# Scheme.net
KiCad netlist of a schematic drawn in Altium Designer
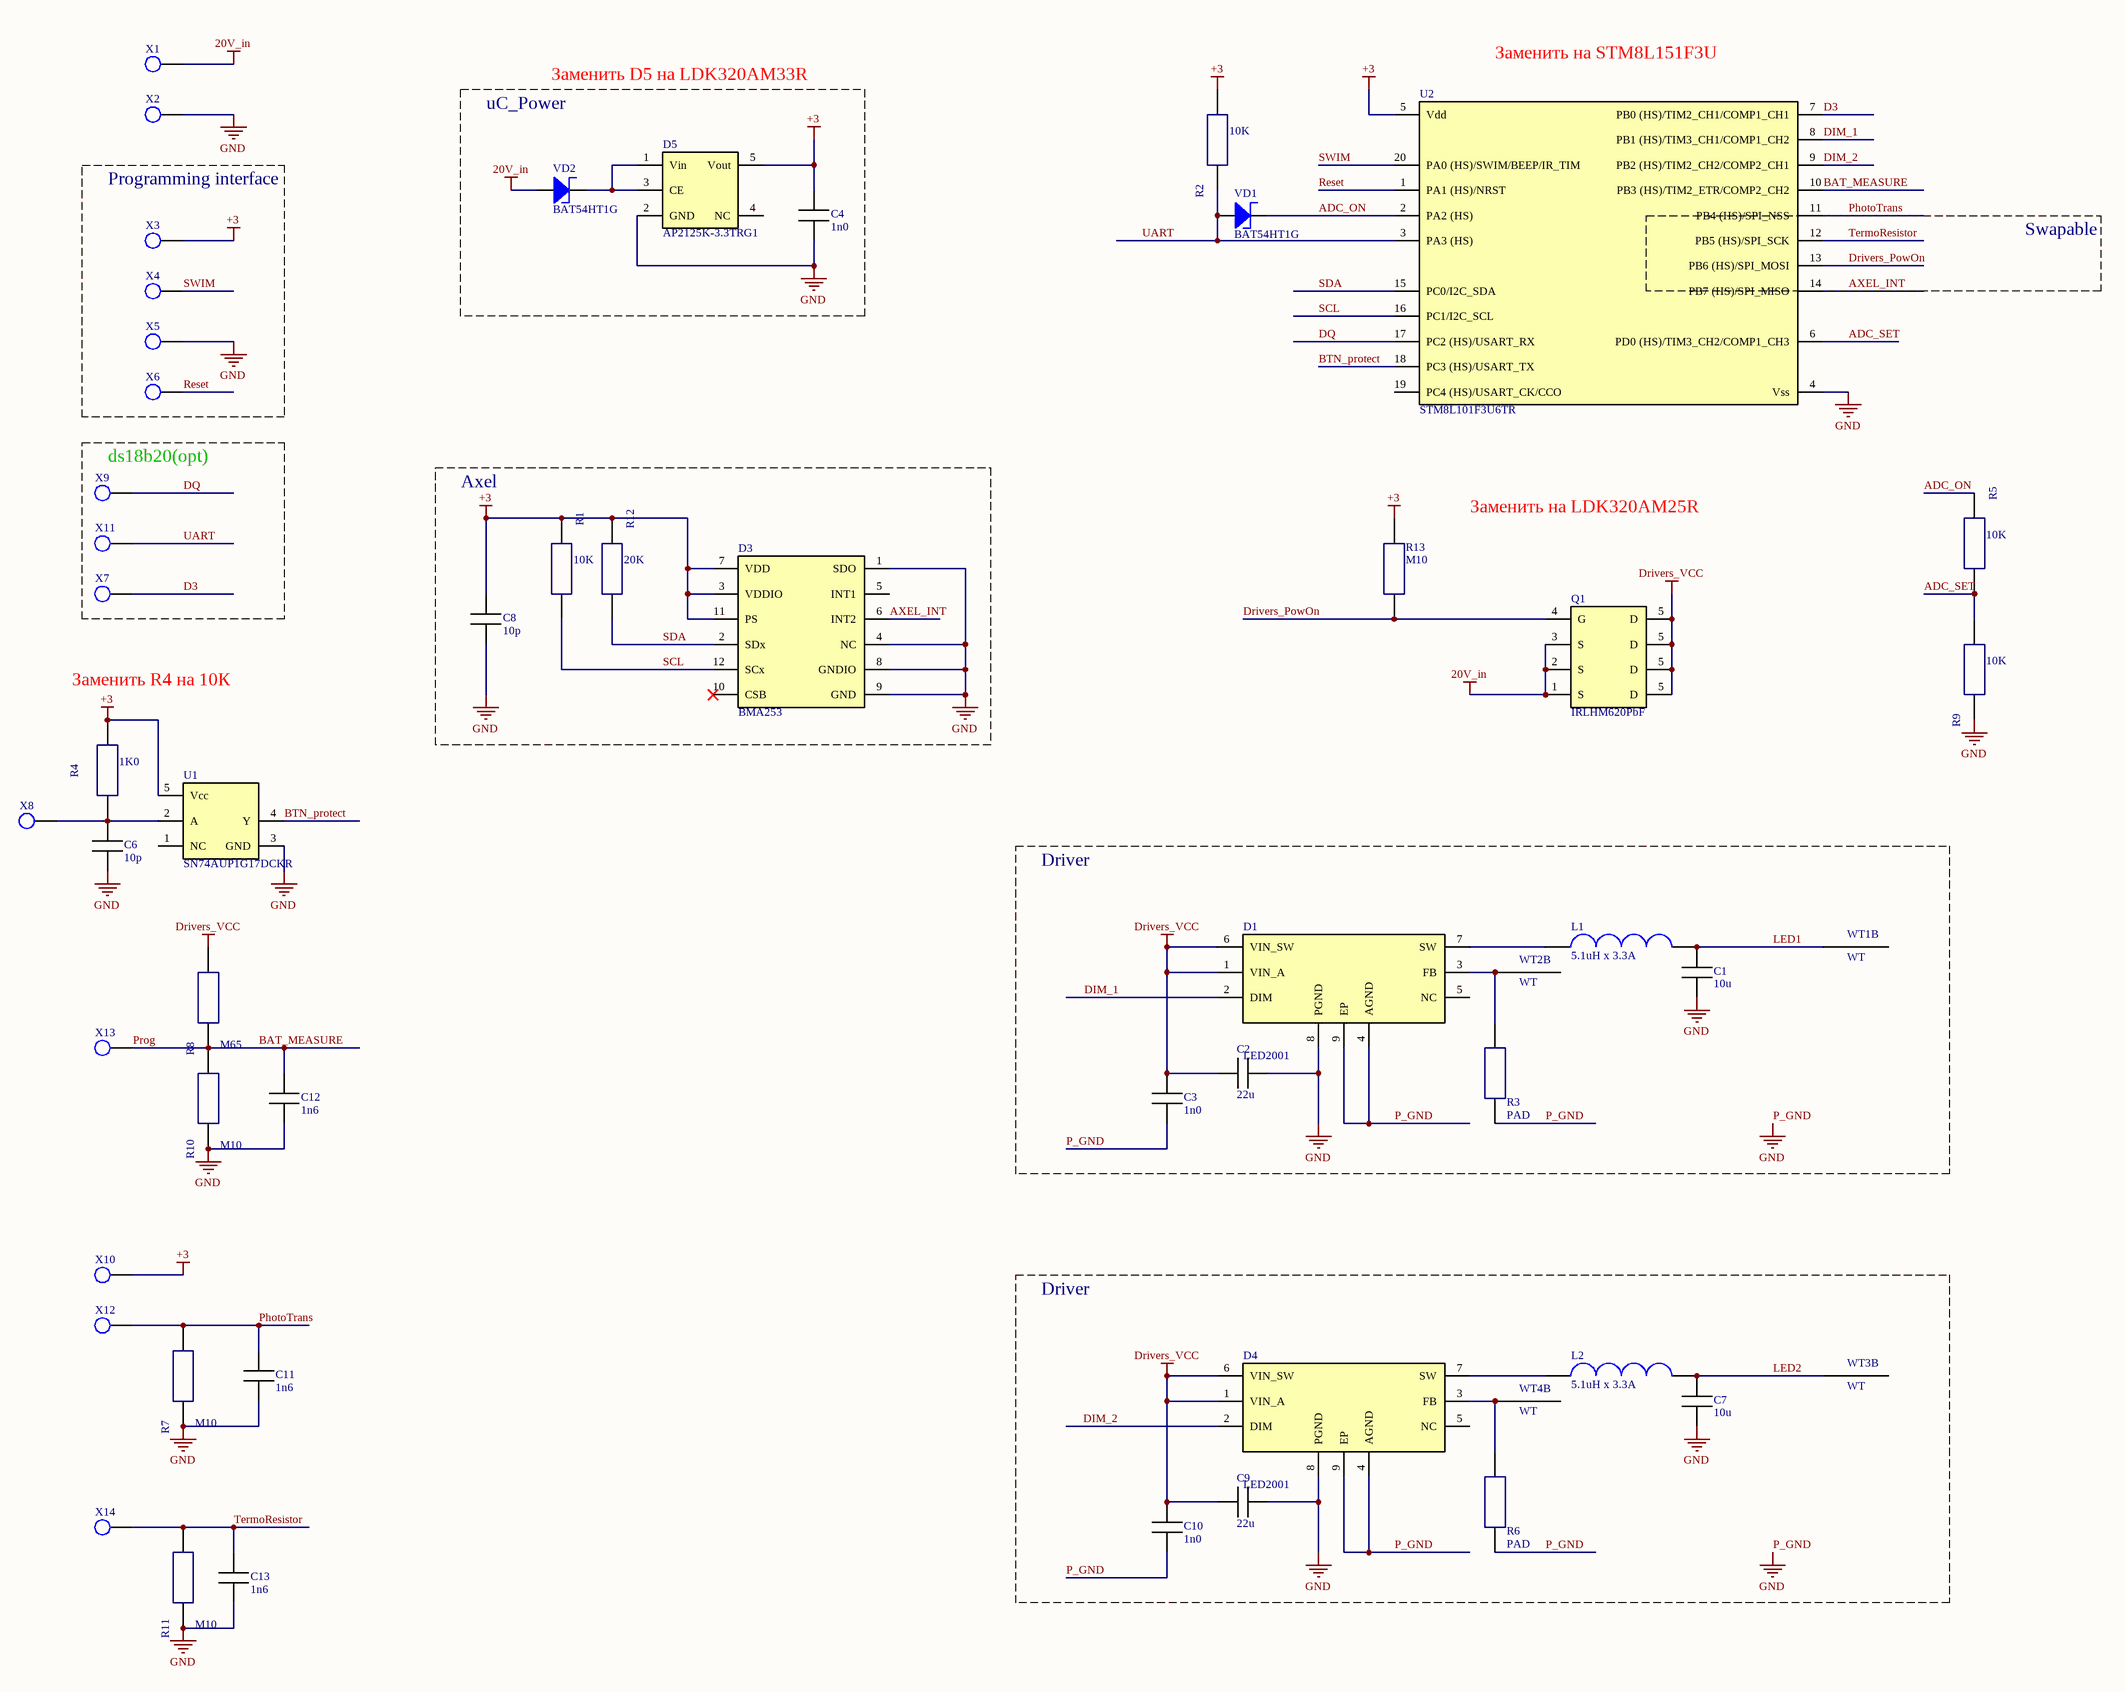
[diagram p0: Scheme.SchDoc]

(export (version "E")
  (design (tool "Eeschema 10.0.6"))
  (components
    (comp (ref "C1")
      (value "10u")
      (footprint "Cap 0603")
      (description "NO")
      (fields (field (name "VOLTAGE") "25V"))
      (libsource (lib "Altium Vault") (part "Capasitor Ceramic"))
    )
    (comp (ref "C2")
      (value "22u")
      (footprint "Cap 1206")
      (description "NO")
      (fields (field (name "VOLTAGE") "25V"))
      (libsource (lib "Altium Vault") (part "Capasitor Ceramic"))
    )
    (comp (ref "C3")
      (value "1n0")
      (footprint "Cap 0603")
      (description "1n x 50V")
      (fields (field (name "VOLTAGE") "50V"))
      (libsource (lib "Altium Vault") (part "Capasitor Ceramic"))
    )
    (comp (ref "C4")
      (value "1n0")
      (footprint "Cap 0603")
      (description "1n x 50V")
      (fields (field (name "VOLTAGE") "50V"))
      (libsource (lib "Altium Vault") (part "Capasitor Ceramic"))
    )
    (comp (ref "C6")
      (value "10p")
      (footprint "Cap 0603")
      (description "10p x 25V")
      (fields (field (name "VOLTAGE") "25V"))
      (libsource (lib "Altium Vault") (part "Capasitor Ceramic"))
    )
    (comp (ref "C7")
      (value "10u")
      (footprint "Cap 0603")
      (description "NO")
      (fields (field (name "VOLTAGE") "25V"))
      (libsource (lib "Altium Vault") (part "Capasitor Ceramic"))
    )
    (comp (ref "C8")
      (value "10p")
      (footprint "Cap 0603")
      (description "10p x 25V")
      (fields (field (name "VOLTAGE") "25V"))
      (libsource (lib "Altium Vault") (part "Capasitor Ceramic"))
    )
    (comp (ref "C9")
      (value "22u")
      (footprint "Cap 1206")
      (description "NO")
      (fields (field (name "VOLTAGE") "25V"))
      (libsource (lib "Altium Vault") (part "Capasitor Ceramic"))
    )
    (comp (ref "C10")
      (value "1n0")
      (footprint "Cap 0603")
      (description "1n x 50V")
      (fields (field (name "VOLTAGE") "50V"))
      (libsource (lib "Altium Vault") (part "Capasitor Ceramic"))
    )
    (comp (ref "C11")
      (value "1n6")
      (footprint "Cap 0603")
      (description "1n6 x 50V")
      (fields (field (name "VOLTAGE") "50V"))
      (libsource (lib "Altium Vault") (part "Capasitor Ceramic"))
    )
    (comp (ref "C12")
      (value "1n6")
      (footprint "Cap 0603")
      (description "1n6 x 50V")
      (fields (field (name "VOLTAGE") "50V"))
      (libsource (lib "Altium Vault") (part "Capasitor Ceramic"))
    )
    (comp (ref "C13")
      (value "1n6")
      (footprint "Cap 0603")
      (description "1n6 x 50V")
      (fields (field (name "VOLTAGE") "50V"))
      (libsource (lib "Altium Vault") (part "Capasitor Ceramic"))
    )
    (comp (ref "D1")
      (value "LED2001")
      (footprint "VQFPN-8 4x4")
      (libsource (lib "Altium Vault") (part "CMP-00546-6"))
    )
    (comp (ref "D3")
      (value "BMA253")
      (footprint "LGA-12 2x2x0.9")
      (libsource (lib "Altium Vault") (part "BMA250E"))
    )
    (comp (ref "D4")
      (value "LED2001")
      (footprint "VQFPN-8 4x4")
      (libsource (lib "Altium Vault") (part "CMP-00546-6"))
    )
    (comp (ref "D5")
      (value "AP2125K-3.3TRG1")
      (footprint "SOT23-5")
      (libsource (lib "Altium Vault") (part "AP2125K-2.8TRG1"))
    )
    (comp (ref "L1")
      (value "5.1uH x 3.3A")
      (footprint "ASPI-6045S-5R1N-T")
      (description "ASPI-6045S-5R1N-T, 5.1uH x 3.3A")
      (fields (field (name "Comment") "51"))
      (libsource (lib "Altium Vault") (part "Inductors"))
    )
    (comp (ref "L2")
      (value "5.1uH x 3.3A")
      (footprint "ASPI-6045S-5R1N-T")
      (description "ASPI-6045S-5R1N-T, 5.1uH x 3.3A")
      (fields (field (name "Comment") "51"))
      (libsource (lib "Altium Vault") (part "Inductors"))
    )
    (comp (ref "Q1")
      (value "IRLHM620PbF")
      (footprint "PQFN-8 3.3x3.3")
      (fields (field (name "Comment") "IRLHM620"))
      (libsource (lib "Altium Vault") (part "IRLHM620PbF"))
    )
    (comp (ref "R1")
      (value "10K")
      (footprint "R0603 5%")
      (description "R 10K")
      (fields (field (name "Comment") "103"))
      (libsource (lib "Altium Vault") (part "Resistors"))
    )
    (comp (ref "R2")
      (value "10K")
      (footprint "R0603 5%")
      (description "R 10K")
      (fields (field (name "Comment") "103"))
      (libsource (lib "Altium Vault") (part "Resistors"))
    )
    (comp (ref "R3")
      (value "PAD")
      (footprint "Resistor 1206")
      (libsource (lib "Altium Vault") (part "Resistors"))
    )
    (comp (ref "R4")
      (value "1K0")
      (footprint "R0603 5%")
      (description "R 1K0")
      (fields (field (name "Comment") "102"))
      (libsource (lib "Altium Vault") (part "Resistors"))
    )
    (comp (ref "R5")
      (value "10K")
      (footprint "R0603 5%")
      (description "R 10K")
      (fields (field (name "Comment") "103"))
      (libsource (lib "Altium Vault") (part "Resistors"))
    )
    (comp (ref "R6")
      (value "PAD")
      (footprint "Resistor 1206")
      (libsource (lib "Altium Vault") (part "Resistors"))
    )
    (comp (ref "R7")
      (value "M10")
      (footprint "R0603 5%")
      (description "R M10")
      (fields (field (name "Comment") "104"))
      (libsource (lib "Altium Vault") (part "Resistors"))
    )
    (comp (ref "R8")
      (value "M65")
      (footprint "R0603 5%")
      (description "R M65")
      (fields (field (name "Comment") "654"))
      (libsource (lib "Altium Vault") (part "Resistors"))
    )
    (comp (ref "R9")
      (value "10K")
      (footprint "R0603 5%")
      (description "R 10K")
      (fields (field (name "Comment") "103"))
      (libsource (lib "Altium Vault") (part "Resistors"))
    )
    (comp (ref "R10")
      (value "M10")
      (footprint "R0603 5%")
      (description "R M10")
      (fields (field (name "Comment") "104"))
      (libsource (lib "Altium Vault") (part "Resistors"))
    )
    (comp (ref "R11")
      (value "M10")
      (footprint "R0603 5%")
      (description "R M10")
      (fields (field (name "Comment") "104"))
      (libsource (lib "Altium Vault") (part "Resistors"))
    )
    (comp (ref "R12")
      (value "20K")
      (footprint "R0603 5%")
      (description "R 20K")
      (fields (field (name "Comment") "203"))
      (libsource (lib "Altium Vault") (part "Resistors"))
    )
    (comp (ref "R13")
      (value "M10")
      (footprint "R0603 5%")
      (description "R M10")
      (fields (field (name "Comment") "104"))
      (libsource (lib "Altium Vault") (part "Resistors"))
    )
    (comp (ref "U1")
      (value "SN74AUP1G17DCKR")
      (footprint "SC-70-5")
      (fields (field (name "Comment") "SN74AUP"))
      (libsource (lib "E-button") (part "SN74AUP1G17DCKR"))
    )
    (comp (ref "U2")
      (value "STM8L101F3U6TR")
      (footprint "UFQFPN20 3x3x0.5")
      (fields (field (name "Comment") "STM8L101"))
      (libsource (lib "Altium Vault") (part "STM8L101x1 UFQFPN-20"))
    )
    (comp (ref "VD1")
      (value "BAT54HT1G")
      (footprint "SOD323")
      (fields (field (name "Comment") "JV"))
      (libsource (lib "Altium Vault") (part "Schottky diode"))
    )
    (comp (ref "VD2")
      (value "BAT54HT1G")
      (footprint "SOD323")
      (fields (field (name "Comment") "JV"))
      (libsource (lib "Altium Vault") (part "Schottky diode"))
    )
    (comp (ref "WT1") (value "WT") (footprint "WT") (libsource (lib "Altium Vault") (part "WireTerminal")))
    (comp (ref "WT2") (value "WT") (footprint "WT") (libsource (lib "Altium Vault") (part "WireTerminal")))
    (comp (ref "WT3") (value "WT") (footprint "WT") (libsource (lib "Altium Vault") (part "WireTerminal")))
    (comp (ref "WT4") (value "WT") (footprint "WT") (libsource (lib "Altium Vault") (part "CMP-00159-3")))
    (comp (ref "X1")
      (value "*")
      (footprint "TP 0.8mm")
      (description "TP 0.8mm")
      (libsource (lib "Altium Vault") (part "Test point"))
    )
    (comp (ref "X2")
      (value "*")
      (footprint "TP 0.8mm")
      (description "TP 0.8mm")
      (libsource (lib "Altium Vault") (part "Test point"))
    )
    (comp (ref "X3")
      (value "*")
      (footprint "TP 0.8mm")
      (description "TP 0.8mm")
      (libsource (lib "Altium Vault") (part "Test point"))
    )
    (comp (ref "X4")
      (value "*")
      (footprint "TP 0.8mm")
      (description "TP 0.8mm")
      (libsource (lib "Altium Vault") (part "Test point"))
    )
    (comp (ref "X5")
      (value "*")
      (footprint "TP 0.8mm")
      (description "TP 0.8mm")
      (libsource (lib "Altium Vault") (part "Test point"))
    )
    (comp (ref "X6")
      (value "*")
      (footprint "TP 0.8mm")
      (description "TP 0.8mm")
      (libsource (lib "Altium Vault") (part "Test point"))
    )
    (comp (ref "X7")
      (value "*")
      (footprint "TP 0.8mm")
      (description "TP 0.8mm")
      (libsource (lib "Altium Vault") (part "Test point"))
    )
    (comp (ref "X8")
      (value "*")
      (footprint "TP 0.8mm")
      (description "TP 0.8mm")
      (libsource (lib "Altium Vault") (part "Test point"))
    )
    (comp (ref "X9")
      (value "*")
      (footprint "TP 0.8mm")
      (description "TP 0.8mm")
      (libsource (lib "Altium Vault") (part "Test point"))
    )
    (comp (ref "X10")
      (value "*")
      (footprint "TP 0.8mm")
      (description "TP 0.8mm")
      (libsource (lib "Altium Vault") (part "Test point"))
    )
    (comp (ref "X11")
      (value "*")
      (footprint "TP 0.8mm")
      (description "TP 0.8mm")
      (libsource (lib "Altium Vault") (part "Test point"))
    )
    (comp (ref "X12")
      (value "*")
      (footprint "TP 0.8mm")
      (description "TP 0.8mm")
      (libsource (lib "Altium Vault") (part "Test point"))
    )
    (comp (ref "X13")
      (value "*")
      (footprint "TP 0.8mm")
      (description "TP 0.8mm")
      (libsource (lib "Altium Vault") (part "Test point"))
    )
    (comp (ref "X14")
      (value "*")
      (footprint "TP 0.8mm")
      (description "TP 0.8mm")
      (libsource (lib "Altium Vault") (part "Test point"))
    )
  )
  (nets
    (net (code "1") (name "+3") (class "Default")
      (node (ref "C4") (pin "2") (pinfunction "2_2") (pintype "passive"))
      (node (ref "C8") (pin "2") (pinfunction "2_2") (pintype "passive"))
      (node (ref "D3") (pin "11") (pinfunction "PS_11") (pintype "passive"))
      (node (ref "D3") (pin "3") (pinfunction "VDDIO_3") (pintype "passive"))
      (node (ref "D3") (pin "7") (pinfunction "VDD_7") (pintype "passive"))
      (node (ref "D5") (pin "5") (pinfunction "Vout_5") (pintype "passive"))
      (node (ref "R1") (pin "1") (pinfunction "1_1") (pintype "passive"))
      (node (ref "R12") (pin "1") (pinfunction "1_1") (pintype "passive"))
      (node (ref "R13") (pin "2") (pinfunction "2_2") (pintype "passive"))
      (node (ref "R2") (pin "2") (pinfunction "2_2") (pintype "passive"))
      (node (ref "R4") (pin "2") (pinfunction "2_2") (pintype "passive"))
      (node (ref "U1") (pin "5") (pinfunction "Vcc_5") (pintype "passive"))
      (node (ref "U2") (pin "5") (pinfunction "Vdd_5") (pintype "passive"))
      (node (ref "X10") (pin "1") (pinfunction "1_1") (pintype "passive"))
      (node (ref "X3") (pin "1") (pinfunction "1_1") (pintype "passive"))
    )
    (net (code "2") (name "/ADC_ON") (class "Default")
      (node (ref "R5") (pin "1") (pinfunction "1_1") (pintype "passive"))
      (node (ref "U2") (pin "2") (pinfunction "PA2_(HS)_2") (pintype "passive"))
      (node (ref "VD1") (pin "1") (pinfunction "1_1") (pintype "passive"))
    )
    (net (code "3") (name "/ADC_SET") (class "Default")
      (node (ref "R5") (pin "2") (pinfunction "2_2") (pintype "passive"))
      (node (ref "R9") (pin "2") (pinfunction "2_2") (pintype "passive"))
      (node (ref "U2") (pin "6") (pinfunction "PD0_(HS)/TIM3_CH2/COMP1_CH3_6") (pintype "passive"))
    )
    (net (code "4") (name "/AXEL_INT") (class "Default")
      (node (ref "D3") (pin "6") (pinfunction "INT2_6") (pintype "passive"))
      (node (ref "U2") (pin "14") (pinfunction "PB7_(HS)/SPI_MISO_14") (pintype "passive"))
    )
    (net (code "5") (name "/BAT_MEASURE") (class "Default")
      (node (ref "C12") (pin "2") (pinfunction "2_2") (pintype "passive"))
      (node (ref "R10") (pin "2") (pinfunction "2_2") (pintype "passive"))
      (node (ref "R8") (pin "1") (pinfunction "1_1") (pintype "passive"))
      (node (ref "U2") (pin "10") (pinfunction "PB3_(HS)/TIM2_ETR/COMP2_CH2_10") (pintype "passive"))
      (node (ref "X13") (pin "1") (pinfunction "1_1") (pintype "passive"))
    )
    (net (code "6") (name "/BTN_protect") (class "Default")
      (node (ref "U1") (pin "4") (pinfunction "Y_4") (pintype "passive"))
      (node (ref "U2") (pin "18") (pinfunction "PC3_(HS)/USART_TX_18") (pintype "passive"))
    )
    (net (code "7") (name "/D3") (class "Default")
      (node (ref "U2") (pin "7") (pinfunction "PB0_(HS)/TIM2_CH1/COMP1_CH1_7") (pintype "passive"))
      (node (ref "X7") (pin "1") (pinfunction "1_1") (pintype "passive"))
    )
    (net (code "8") (name "/DIM_1") (class "Default")
      (node (ref "D1") (pin "2") (pinfunction "DIM_2") (pintype "passive"))
      (node (ref "U2") (pin "8") (pinfunction "PB1_(HS)/TIM3_CH1/COMP1_CH2_8") (pintype "passive"))
    )
    (net (code "9") (name "/DIM_2") (class "Default")
      (node (ref "D4") (pin "2") (pinfunction "DIM_2") (pintype "passive"))
      (node (ref "U2") (pin "9") (pinfunction "PB2_(HS)/TIM2_CH2/COMP2_CH1_9") (pintype "passive"))
    )
    (net (code "10") (name "/DQ") (class "Default")
      (node (ref "U2") (pin "17") (pinfunction "PC2_(HS)/USART_RX_17") (pintype "passive"))
      (node (ref "X9") (pin "1") (pinfunction "1_1") (pintype "passive"))
    )
    (net (code "11") (name "/Drivers_PowOn") (class "Default")
      (node (ref "Q1") (pin "4") (pinfunction "G_4") (pintype "passive"))
      (node (ref "R13") (pin "1") (pinfunction "1_1") (pintype "passive"))
      (node (ref "U2") (pin "13") (pinfunction "PB6_(HS)/SPI_MOSI_13") (pintype "passive"))
    )
    (net (code "12") (name "/LED1") (class "Default")
      (node (ref "C1") (pin "2") (pinfunction "2_2") (pintype "passive"))
      (node (ref "L1") (pin "2") (pinfunction "2_2") (pintype "passive"))
      (node (ref "WT1") (pin "1") (pinfunction "1_1") (pintype "passive"))
    )
    (net (code "13") (name "/LED2") (class "Default")
      (node (ref "C7") (pin "2") (pinfunction "2_2") (pintype "passive"))
      (node (ref "L2") (pin "2") (pinfunction "2_2") (pintype "passive"))
      (node (ref "WT3") (pin "1") (pinfunction "1_1") (pintype "passive"))
    )
    (net (code "14") (name "/PhotoTrans") (class "Default")
      (node (ref "C11") (pin "2") (pinfunction "2_2") (pintype "passive"))
      (node (ref "R7") (pin "2") (pinfunction "2_2") (pintype "passive"))
      (node (ref "U2") (pin "11") (pinfunction "PB4_(HS)/SPI_NSS_11") (pintype "passive"))
      (node (ref "X12") (pin "1") (pinfunction "1_1") (pintype "passive"))
    )
    (net (code "15") (name "/Reset") (class "Default")
      (node (ref "U2") (pin "1") (pinfunction "PA1_(HS)/NRST_1") (pintype "passive"))
      (node (ref "X6") (pin "1") (pinfunction "1_1") (pintype "passive"))
    )
    (net (code "16") (name "/SCL") (class "Default")
      (node (ref "D3") (pin "12") (pinfunction "SCx_12") (pintype "passive"))
      (node (ref "R1") (pin "2") (pinfunction "2_2") (pintype "passive"))
      (node (ref "U2") (pin "16") (pinfunction "PC1/I2C_SCL_16") (pintype "passive"))
    )
    (net (code "17") (name "/SDA") (class "Default")
      (node (ref "D3") (pin "2") (pinfunction "SDx_2") (pintype "passive"))
      (node (ref "R12") (pin "2") (pinfunction "2_2") (pintype "passive"))
      (node (ref "U2") (pin "15") (pinfunction "PC0/I2C_SDA_15") (pintype "passive"))
    )
    (net (code "18") (name "/SWIM") (class "Default")
      (node (ref "U2") (pin "20") (pinfunction "PA0_(HS)/SWIM/BEEP/IR_TIM_20") (pintype "passive"))
      (node (ref "X4") (pin "1") (pinfunction "1_1") (pintype "passive"))
    )
    (net (code "19") (name "/TermoResistor") (class "Default")
      (node (ref "C13") (pin "2") (pinfunction "2_2") (pintype "passive"))
      (node (ref "R11") (pin "2") (pinfunction "2_2") (pintype "passive"))
      (node (ref "U2") (pin "12") (pinfunction "PB5_(HS)/SPI_SCK_12") (pintype "passive"))
      (node (ref "X14") (pin "1") (pinfunction "1_1") (pintype "passive"))
    )
    (net (code "20") (name "/UART") (class "Default")
      (node (ref "R2") (pin "1") (pinfunction "1_1") (pintype "passive"))
      (node (ref "U2") (pin "3") (pinfunction "PA3_(HS)_3") (pintype "passive"))
      (node (ref "VD1") (pin "2") (pinfunction "2_2") (pintype "passive"))
      (node (ref "X11") (pin "1") (pinfunction "1_1") (pintype "passive"))
    )
    (net (code "21") (name "20V_in") (class "Default")
      (node (ref "Q1") (pin "1") (pinfunction "S_1") (pintype "passive"))
      (node (ref "Q1") (pin "2") (pinfunction "S_2") (pintype "passive"))
      (node (ref "Q1") (pin "3") (pinfunction "S_3") (pintype "passive"))
      (node (ref "VD2") (pin "2") (pinfunction "2_2") (pintype "passive"))
      (node (ref "X1") (pin "1") (pinfunction "1_1") (pintype "passive"))
    )
    (net (code "22") (name "Drivers_VCC") (class "Default")
      (node (ref "C10") (pin "2") (pinfunction "2_2") (pintype "passive"))
      (node (ref "C2") (pin "1") (pinfunction "1_1") (pintype "passive"))
      (node (ref "C3") (pin "2") (pinfunction "2_2") (pintype "passive"))
      (node (ref "C9") (pin "1") (pinfunction "1_1") (pintype "passive"))
      (node (ref "D1") (pin "1") (pinfunction "VIN_A_1") (pintype "passive"))
      (node (ref "D1") (pin "6") (pinfunction "VIN_SW_6") (pintype "passive"))
      (node (ref "D4") (pin "1") (pinfunction "VIN_A_1") (pintype "passive"))
      (node (ref "D4") (pin "6") (pinfunction "VIN_SW_6") (pintype "passive"))
      (node (ref "Q1") (pin "5") (pinfunction "D_5") (pintype "passive"))
      (node (ref "R8") (pin "2") (pinfunction "2_2") (pintype "passive"))
    )
    (net (code "23") (name "GND") (class "Default")
      (node (ref "C1") (pin "1") (pinfunction "1_1") (pintype "passive"))
      (node (ref "C10") (pin "1") (pinfunction "1_1") (pintype "passive"))
      (node (ref "C11") (pin "1") (pinfunction "1_1") (pintype "passive"))
      (node (ref "C12") (pin "1") (pinfunction "1_1") (pintype "passive"))
      (node (ref "C13") (pin "1") (pinfunction "1_1") (pintype "passive"))
      (node (ref "C2") (pin "2") (pinfunction "2_2") (pintype "passive"))
      (node (ref "C3") (pin "1") (pinfunction "1_1") (pintype "passive"))
      (node (ref "C4") (pin "1") (pinfunction "1_1") (pintype "passive"))
      (node (ref "C6") (pin "1") (pinfunction "1_1") (pintype "passive"))
      (node (ref "C7") (pin "1") (pinfunction "1_1") (pintype "passive"))
      (node (ref "C8") (pin "1") (pinfunction "1_1") (pintype "passive"))
      (node (ref "C9") (pin "2") (pinfunction "2_2") (pintype "passive"))
      (node (ref "D1") (pin "4") (pinfunction "AGND_4") (pintype "passive"))
      (node (ref "D1") (pin "8") (pinfunction "PGND_8") (pintype "passive"))
      (node (ref "D1") (pin "9") (pinfunction "EP_9") (pintype "passive"))
      (node (ref "D3") (pin "1") (pinfunction "SDO_1") (pintype "passive"))
      (node (ref "D3") (pin "4") (pinfunction "NC_4") (pintype "passive"))
      (node (ref "D3") (pin "8") (pinfunction "GNDIO_8") (pintype "passive"))
      (node (ref "D3") (pin "9") (pinfunction "GND_9") (pintype "passive"))
      (node (ref "D4") (pin "4") (pinfunction "AGND_4") (pintype "passive"))
      (node (ref "D4") (pin "8") (pinfunction "PGND_8") (pintype "passive"))
      (node (ref "D4") (pin "9") (pinfunction "EP_9") (pintype "passive"))
      (node (ref "D5") (pin "2") (pinfunction "GND_2") (pintype "passive"))
      (node (ref "R10") (pin "1") (pinfunction "1_1") (pintype "passive"))
      (node (ref "R11") (pin "1") (pinfunction "1_1") (pintype "passive"))
      (node (ref "R3") (pin "1") (pinfunction "1_1") (pintype "passive"))
      (node (ref "R6") (pin "1") (pinfunction "1_1") (pintype "passive"))
      (node (ref "R7") (pin "1") (pinfunction "1_1") (pintype "passive"))
      (node (ref "R9") (pin "1") (pinfunction "1_1") (pintype "passive"))
      (node (ref "U1") (pin "3") (pinfunction "GND_3") (pintype "passive"))
      (node (ref "U2") (pin "4") (pinfunction "Vss_4") (pintype "passive"))
      (node (ref "X2") (pin "1") (pinfunction "1_1") (pintype "passive"))
      (node (ref "X5") (pin "1") (pinfunction "1_1") (pintype "passive"))
    )
    (net (code "24") (name "Net-(D1-FB)") (class "Default")
      (node (ref "D1") (pin "3") (pinfunction "FB_3") (pintype "passive"))
      (node (ref "R3") (pin "2") (pinfunction "2_2") (pintype "passive"))
      (node (ref "WT2") (pin "1") (pinfunction "1_1") (pintype "passive"))
    )
    (net (code "25") (name "Net-(D1-SW)") (class "Default")
      (node (ref "D1") (pin "7") (pinfunction "SW_7") (pintype "passive"))
      (node (ref "L1") (pin "1") (pinfunction "1_1") (pintype "passive"))
    )
    (net (code "26") (name "Net-(D4-FB)") (class "Default")
      (node (ref "D4") (pin "3") (pinfunction "FB_3") (pintype "passive"))
      (node (ref "R6") (pin "2") (pinfunction "2_2") (pintype "passive"))
      (node (ref "WT4") (pin "1") (pinfunction "1_1") (pintype "passive"))
    )
    (net (code "27") (name "Net-(D4-SW)") (class "Default")
      (node (ref "D4") (pin "7") (pinfunction "SW_7") (pintype "passive"))
      (node (ref "L2") (pin "1") (pinfunction "1_1") (pintype "passive"))
    )
    (net (code "28") (name "Net-(D5-CE)") (class "Default")
      (node (ref "D5") (pin "1") (pinfunction "Vin_1") (pintype "passive"))
      (node (ref "D5") (pin "3") (pinfunction "CE_3") (pintype "passive"))
      (node (ref "VD2") (pin "1") (pinfunction "1_1") (pintype "passive"))
    )
    (net (code "29") (name "Net-(U1-A)") (class "Default")
      (node (ref "C6") (pin "2") (pinfunction "2_2") (pintype "passive"))
      (node (ref "R4") (pin "1") (pinfunction "1_1") (pintype "passive"))
      (node (ref "U1") (pin "2") (pinfunction "A_2") (pintype "passive"))
      (node (ref "X8") (pin "1") (pinfunction "1_1") (pintype "passive"))
    )
    (net (code "30") (name "unconnected-(D1-NC-Pad5)") (class "Default")
      (node (ref "D1") (pin "5") (pinfunction "NC_5") (pintype "passive"))
    )
    (net (code "31") (name "unconnected-(D3-CSB-Pad10)") (class "Default")
      (node (ref "D3") (pin "10") (pinfunction "CSB_10") (pintype "passive+no_connect"))
    )
    (net (code "32") (name "unconnected-(D3-INT1-Pad5)") (class "Default")
      (node (ref "D3") (pin "5") (pinfunction "INT1_5") (pintype "passive"))
    )
    (net (code "33") (name "unconnected-(D4-NC-Pad5)") (class "Default")
      (node (ref "D4") (pin "5") (pinfunction "NC_5") (pintype "passive"))
    )
    (net (code "34") (name "unconnected-(D5-NC-Pad4)") (class "Default")
      (node (ref "D5") (pin "4") (pinfunction "NC_4") (pintype "passive"))
    )
    (net (code "35") (name "unconnected-(U1-NC-Pad1)") (class "Default")
      (node (ref "U1") (pin "1") (pinfunction "NC_1") (pintype "passive"))
    )
    (net (code "36") (name "unconnected-(U2-PC4_(HS){slash}USART_CK{slash}CCO-Pad19)") (class "Default")
      (node (ref "U2") (pin "19") (pinfunction "PC4_(HS)/USART_CK/CCO_19") (pintype "passive"))
    )
  )
)
